# 10-Channel_SPI_Sensing_Circuit.net
KiCad netlist of a schematic drawn in Altium Designer
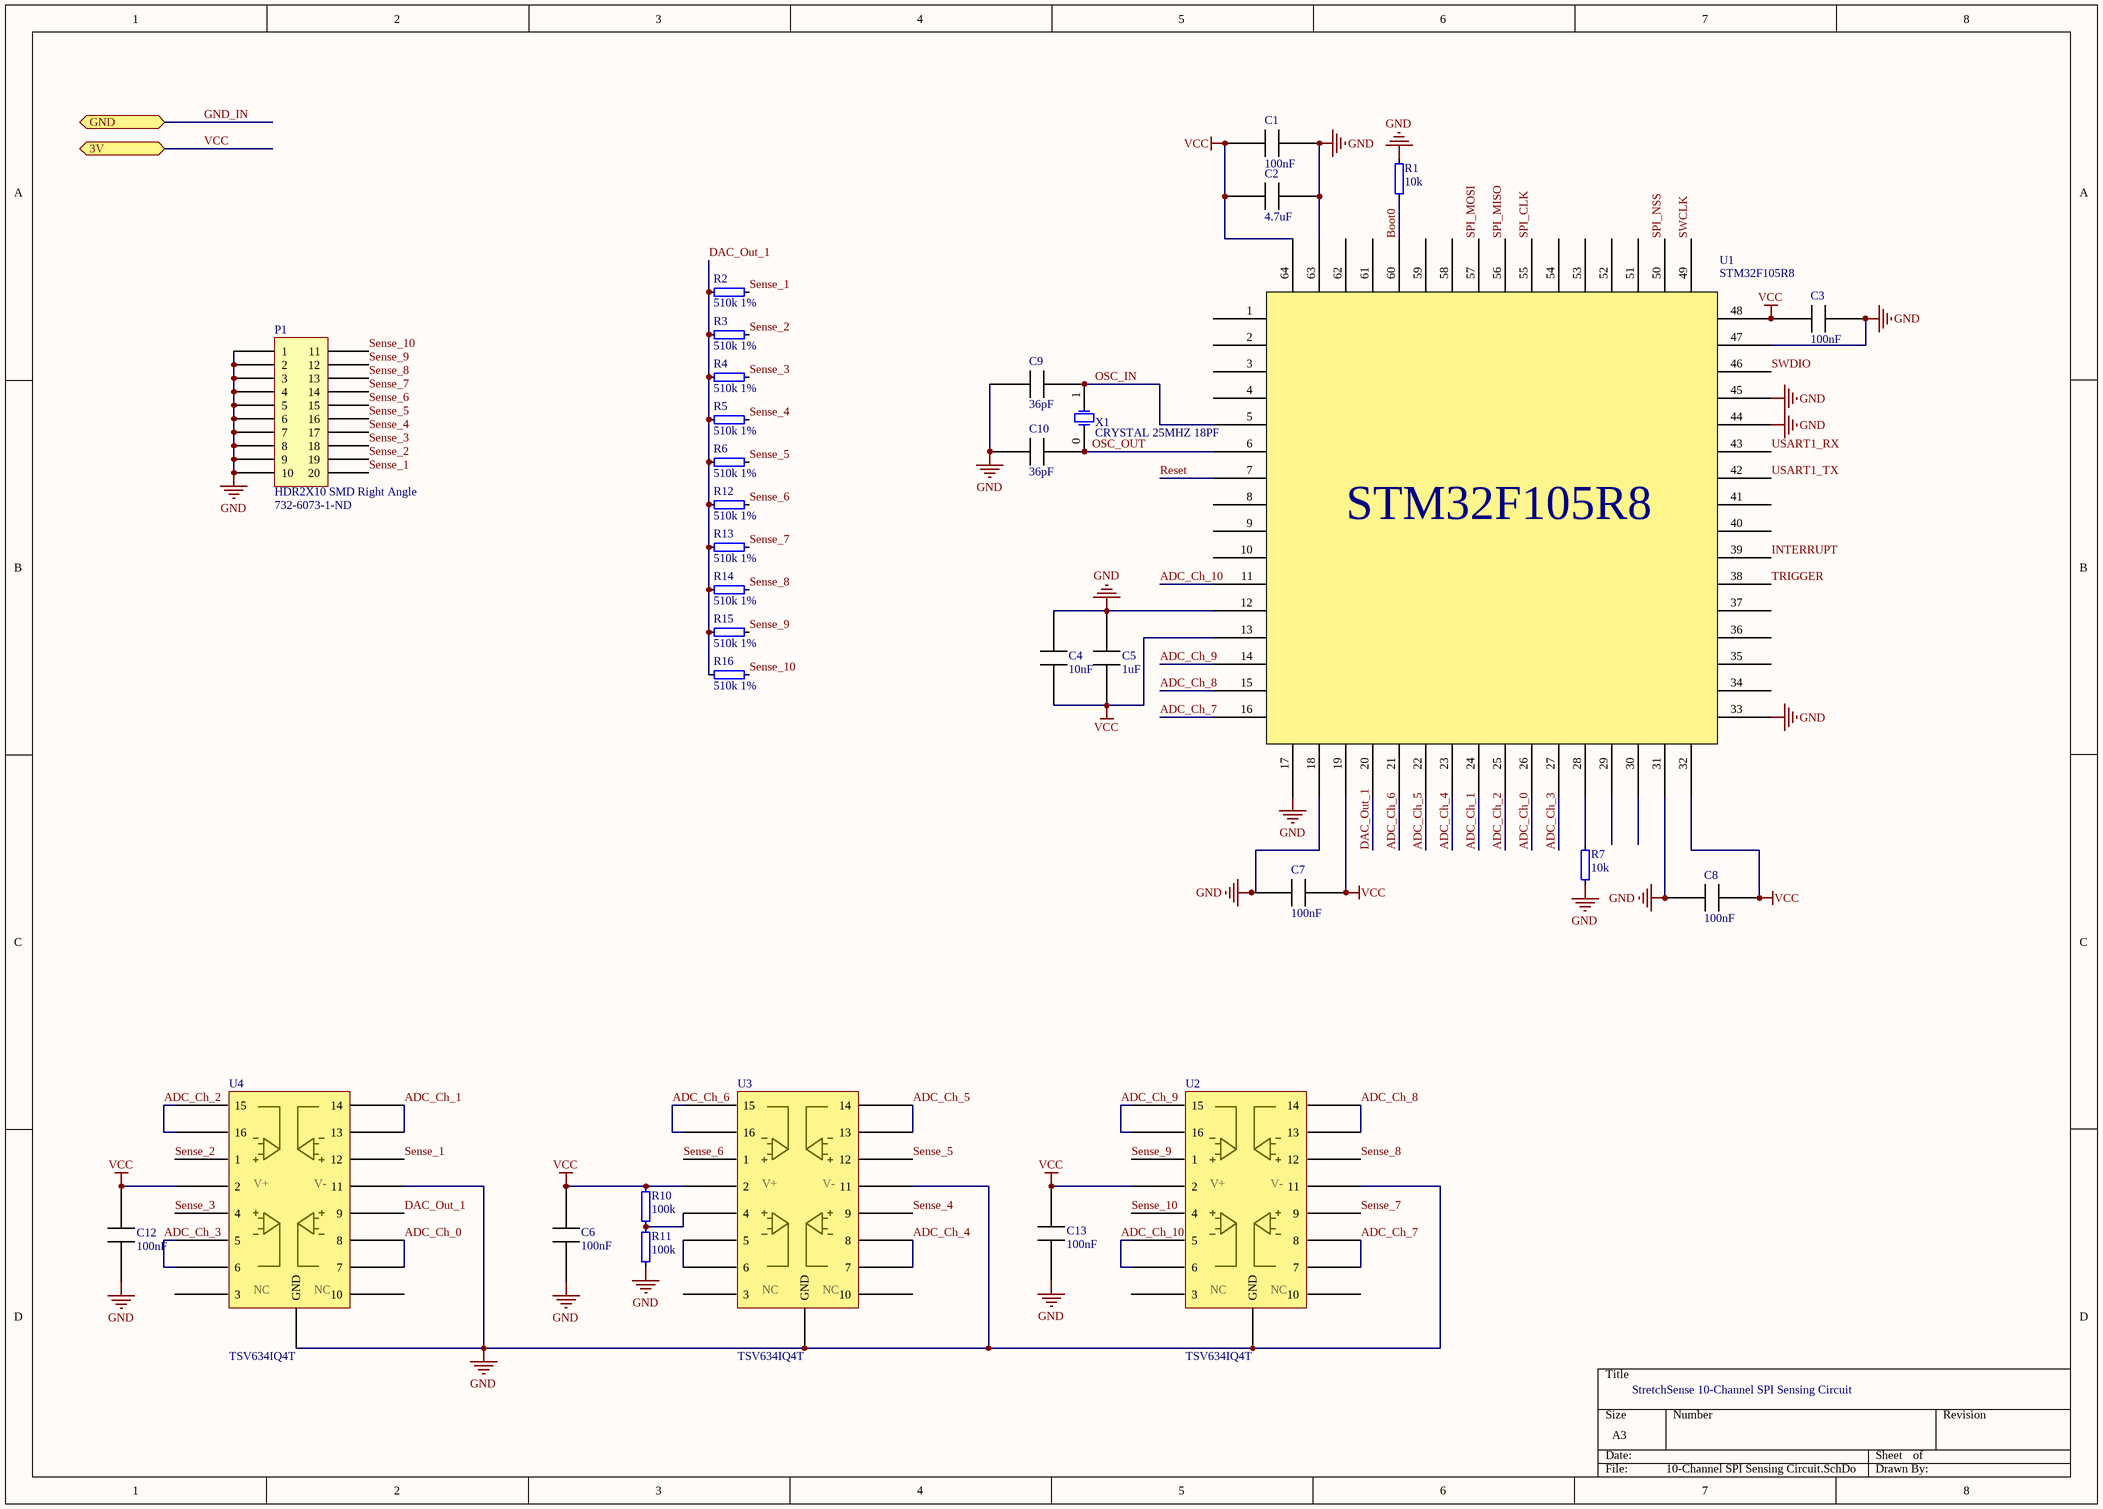
[diagram p0: 10-Channel SPI Sensing Circuit.SchDoc]

(export (version "E")
  (design (tool "Eeschema 10.0.6"))
  (components
    (comp (ref "C1")
      (value "100nF")
      (footprint "0402 Cap")
      (description "Capacitor")
      (fields
        (field (name "MANUFACTURER") "Samsung Electro-Mechanics America, Inc.")
        (field (name "MANUFACTURER PART NUMBER") "CL05B104KO5NNNC")
      )
      (libsource (lib "Fugu_V1") (part "Cap 0402 100nF 10%"))
    )
    (comp (ref "C2")
      (value "4.7uF")
      (footprint "0402 Cap")
      (description "Capacitor")
      (fields
        (field (name "MANUFACTURER") "TDK Corporation")
        (field (name "MANUFACTURER PART NUMBER") "C1005X5R1A475K050BC")
      )
      (libsource (lib "Gen3_V1") (part "Cap 0402 4.7uF 10%"))
    )
    (comp (ref "C3")
      (value "100nF")
      (footprint "0402 Cap")
      (description "Capacitor")
      (fields
        (field (name "MANUFACTURER") "Samsung Electro-Mechanics America, Inc.")
        (field (name "MANUFACTURER PART NUMBER") "CL05B104KO5NNNC")
      )
      (libsource (lib "Fugu_V1") (part "Cap 0402 100nF 10%"))
    )
    (comp (ref "C4")
      (value "10nF")
      (footprint "0402 Cap")
      (description "Capacitor")
      (fields
        (field (name "MANUFACTURER") "Samsung Electro-Mechanics America, Inc.")
        (field (name "MANUFACTURER PART NUMBER") "CL05B103KA5NNNC")
      )
      (libsource (lib "Gen3_V1") (part "Cap 0402 10nF 10%"))
    )
    (comp (ref "C5")
      (value "1uF")
      (footprint "0402 Cap")
      (description "Capacitor")
      (fields
        (field (name "MANUFACTURER") "Samsung Electro-Mechanics America, Inc.")
        (field (name "MANUFACTURER PART NUMBER") "CL05A105JQ5NNNC")
      )
      (libsource (lib "Fugu_V1") (part "Cap 0402 1uF 5%"))
    )
    (comp (ref "C6")
      (value "100nF")
      (footprint "0402 Cap")
      (description "Capacitor")
      (fields
        (field (name "MANUFACTURER") "Samsung Electro-Mechanics America, Inc.")
        (field (name "MANUFACTURER PART NUMBER") "CL05B104KO5NNNC")
      )
      (libsource (lib "Fugu_V1") (part "Cap 0402 100nF 10%"))
    )
    (comp (ref "C7")
      (value "100nF")
      (footprint "0402 Cap")
      (description "Capacitor")
      (fields
        (field (name "MANUFACTURER") "Samsung Electro-Mechanics America, Inc.")
        (field (name "MANUFACTURER PART NUMBER") "CL05B104KO5NNNC")
      )
      (libsource (lib "Fugu_V1") (part "Cap 0402 100nF 10%"))
    )
    (comp (ref "C8")
      (value "100nF")
      (footprint "0402 Cap")
      (description "Capacitor")
      (fields
        (field (name "MANUFACTURER") "Samsung Electro-Mechanics America, Inc.")
        (field (name "MANUFACTURER PART NUMBER") "CL05B104KO5NNNC")
      )
      (libsource (lib "Fugu_V1") (part "Cap 0402 100nF 10%"))
    )
    (comp (ref "C9")
      (value "36pF")
      (footprint "0402 Cap")
      (description "Capacitor")
      (fields
        (field (name "MANUFACTURER") "Samsung Electro-Mechanics America, Inc.")
        (field (name "MANUFACTURER PART NUMBER") "CL05C360JB5NNNC")
      )
      (libsource (lib "Fugu_V1") (part "Cap 36pF 0402"))
    )
    (comp (ref "C10")
      (value "36pF")
      (footprint "0402 Cap")
      (description "Capacitor")
      (fields
        (field (name "MANUFACTURER") "Samsung Electro-Mechanics America, Inc.")
        (field (name "MANUFACTURER PART NUMBER") "CL05C360JB5NNNC")
      )
      (libsource (lib "Fugu_V1") (part "Cap 36pF 0402"))
    )
    (comp (ref "C12")
      (value "100nF")
      (footprint "0402 Cap")
      (description "Capacitor")
      (fields
        (field (name "MANUFACTURER") "Samsung Electro-Mechanics America, Inc.")
        (field (name "MANUFACTURER PART NUMBER") "CL05B104KO5NNNC")
      )
      (libsource (lib "Fugu_V1") (part "Cap 0402 100nF 10%"))
    )
    (comp (ref "C13")
      (value "100nF")
      (footprint "0402 Cap")
      (description "Capacitor")
      (fields
        (field (name "MANUFACTURER") "Samsung Electro-Mechanics America, Inc.")
        (field (name "MANUFACTURER PART NUMBER") "CL05B104KO5NNNC")
      )
      (libsource (lib "Fugu_V1") (part "Cap 0402 100nF 10%"))
    )
    (comp (ref "P1")
      (value "HDR2X10 SMD Right Angle")
      (footprint "HDR2X10 SMD RIGHT")
      (description "Header")
      (fields
        (field (name "MANUFACTURER") "Wurth Electronics Inc")
        (field (name "MANUFACTURER PART NUMBER") "610120249121")
        (field (name "SUPPLIER PART NUMBER 1") "732-6073-1-ND")
      )
      (libsource (lib "Gen3_V1") (part "Header 2x10 SMD R/A 2.54mm"))
    )
    (comp (ref "R1")
      (value "10k")
      (footprint "0402 Res")
      (description "Resistor")
      (fields
        (field (name "MANUFACTURER") "Yageo")
        (field (name "MANUFACTURER PART NUMBER") "RC0402JR-0710KL")
      )
      (libsource (lib "Fugu_V1") (part "Res 0402 10k 5%"))
    )
    (comp (ref "R2")
      (value "510k 1%")
      (footprint "0402 Res")
      (description "Resistor")
      (fields
        (field (name "MANUFACTURER") "Yageo")
        (field (name "MANUFACTURER PART NUMBER") "RC0402FR-07510KL")
      )
      (libsource (lib "Fugu_V1") (part "Res 0402 510k 1%"))
    )
    (comp (ref "R3")
      (value "510k 1%")
      (footprint "0402 Res")
      (description "Resistor")
      (fields
        (field (name "MANUFACTURER") "Yageo")
        (field (name "MANUFACTURER PART NUMBER") "RC0402FR-07510KL")
      )
      (libsource (lib "Fugu_V1") (part "Res 0402 510k 1%"))
    )
    (comp (ref "R4")
      (value "510k 1%")
      (footprint "0402 Res")
      (description "Resistor")
      (fields
        (field (name "MANUFACTURER") "Yageo")
        (field (name "MANUFACTURER PART NUMBER") "RC0402FR-07510KL")
      )
      (libsource (lib "Fugu_V1") (part "Res 0402 510k 1%"))
    )
    (comp (ref "R5")
      (value "510k 1%")
      (footprint "0402 Res")
      (description "Resistor")
      (fields
        (field (name "MANUFACTURER") "Yageo")
        (field (name "MANUFACTURER PART NUMBER") "RC0402FR-07510KL")
      )
      (libsource (lib "Fugu_V1") (part "Res 0402 510k 1%"))
    )
    (comp (ref "R6")
      (value "510k 1%")
      (footprint "0402 Res")
      (description "Resistor")
      (fields
        (field (name "MANUFACTURER") "Yageo")
        (field (name "MANUFACTURER PART NUMBER") "RC0402FR-07510KL")
      )
      (libsource (lib "Fugu_V1") (part "Res 0402 510k 1%"))
    )
    (comp (ref "R7")
      (value "10k")
      (footprint "0402 Res")
      (description "Resistor")
      (fields
        (field (name "MANUFACTURER") "Yageo")
        (field (name "MANUFACTURER PART NUMBER") "RC0402JR-0710KL")
      )
      (libsource (lib "Fugu_V1") (part "Res 0402 10k 5%"))
    )
    (comp (ref "R10")
      (value "100k")
      (footprint "0402 Res")
      (description "Resistor")
      (fields
        (field (name "MANUFACTURER") "Yageo")
        (field (name "MANUFACTURER PART NUMBER") "RC0402FR-07100KL")
      )
      (libsource (lib "Fugu_V1") (part "Res 0402 100k 5%"))
    )
    (comp (ref "R11")
      (value "100k")
      (footprint "0402 Res")
      (description "Resistor")
      (fields
        (field (name "MANUFACTURER") "Yageo")
        (field (name "MANUFACTURER PART NUMBER") "RC0402FR-07100KL")
      )
      (libsource (lib "Fugu_V1") (part "Res 0402 100k 5%"))
    )
    (comp (ref "R12")
      (value "510k 1%")
      (footprint "0402 Res")
      (description "Resistor")
      (fields
        (field (name "MANUFACTURER") "Yageo")
        (field (name "MANUFACTURER PART NUMBER") "RC0402FR-07510KL")
      )
      (libsource (lib "Fugu_V1") (part "Res 0402 510k 1%"))
    )
    (comp (ref "R13")
      (value "510k 1%")
      (footprint "0402 Res")
      (description "Resistor")
      (fields
        (field (name "MANUFACTURER") "Yageo")
        (field (name "MANUFACTURER PART NUMBER") "RC0402FR-07510KL")
      )
      (libsource (lib "Fugu_V1") (part "Res 0402 510k 1%"))
    )
    (comp (ref "R14")
      (value "510k 1%")
      (footprint "0402 Res")
      (description "Resistor")
      (fields
        (field (name "MANUFACTURER") "Yageo")
        (field (name "MANUFACTURER PART NUMBER") "RC0402FR-07510KL")
      )
      (libsource (lib "Fugu_V1") (part "Res 0402 510k 1%"))
    )
    (comp (ref "R15")
      (value "510k 1%")
      (footprint "0402 Res")
      (description "Resistor")
      (fields
        (field (name "MANUFACTURER") "Yageo")
        (field (name "MANUFACTURER PART NUMBER") "RC0402FR-07510KL")
      )
      (libsource (lib "Fugu_V1") (part "Res 0402 510k 1%"))
    )
    (comp (ref "R16")
      (value "510k 1%")
      (footprint "0402 Res")
      (description "Resistor")
      (fields
        (field (name "MANUFACTURER") "Yageo")
        (field (name "MANUFACTURER PART NUMBER") "RC0402FR-07510KL")
      )
      (libsource (lib "Fugu_V1") (part "Res 0402 510k 1%"))
    )
    (comp (ref "U1")
      (value "STM32F105R8")
      (footprint "STM32F105R8")
      (description "Microcontroller")
      (fields
        (field (name "PART") "ST Microelectronics STM32F105R8")
        (field (name "MANUFACTURER") "STMicroelectronics")
      )
      (libsource (lib "Fugu_V1") (part "STM32F105R8"))
    )
    (comp (ref "U2")
      (value "TSV634IQ4T")
      (footprint "QFN-16")
      (description "Quad Opamp")
      (fields (field (name "MANUFACTURER") "STMicroelectronics"))
      (libsource (lib "Fugu_V1") (part "Quad Opamp TSV634IQ4T"))
    )
    (comp (ref "U3")
      (value "TSV634IQ4T")
      (footprint "QFN-16")
      (description "Quad Opamp")
      (fields (field (name "MANUFACTURER") "STMicroelectronics"))
      (libsource (lib "Fugu_V1") (part "Quad Opamp TSV634IQ4T"))
    )
    (comp (ref "U4")
      (value "TSV634IQ4T")
      (footprint "QFN-16")
      (description "Quad Opamp")
      (fields (field (name "MANUFACTURER") "STMicroelectronics"))
      (libsource (lib "Fugu_V1") (part "Quad Opamp TSV634IQ4T"))
    )
    (comp (ref "X1")
      (value "CRYSTAL 25MHZ 18PF")
      (footprint "CRYSTAL 24MHZ 18PF SMD")
      (description "445C25D24M00000")
      (fields
        (field (name "MANUFACTURER") "CTS-Frequency Controls")
        (field (name "MANUFACTURER PART NUMBER") "445C25D25M00000")
      )
      (libsource (lib "Gen3_V1") (part "CRYSTAL 25MHZ 18PF SMD"))
    )
  )
  (nets
    (net (code "1") (name "/ADC_Ch_0") (class "Default")
      (node (ref "U1") (pin "26") (pinfunction "Pin26_26") (pintype "passive"))
      (node (ref "U4") (pin "7") (pinfunction "7_7") (pintype "passive"))
      (node (ref "U4") (pin "8") (pinfunction "8_8") (pintype "passive"))
    )
    (net (code "2") (name "/ADC_Ch_1") (class "Default")
      (node (ref "U1") (pin "24") (pinfunction "Pin24_24") (pintype "passive"))
      (node (ref "U4") (pin "13") (pinfunction "13_13") (pintype "passive"))
      (node (ref "U4") (pin "14") (pinfunction "14_14") (pintype "passive"))
    )
    (net (code "3") (name "/ADC_Ch_2") (class "Default")
      (node (ref "U1") (pin "25") (pinfunction "Pin25_25") (pintype "passive"))
      (node (ref "U4") (pin "15") (pinfunction "15_15") (pintype "passive"))
      (node (ref "U4") (pin "16") (pinfunction "16_16") (pintype "passive"))
    )
    (net (code "4") (name "/ADC_Ch_3") (class "Default")
      (node (ref "U1") (pin "27") (pinfunction "Pin27_27") (pintype "passive"))
      (node (ref "U4") (pin "5") (pinfunction "5_5") (pintype "passive"))
      (node (ref "U4") (pin "6") (pinfunction "6_6") (pintype "passive"))
    )
    (net (code "5") (name "/ADC_Ch_4") (class "Default")
      (node (ref "U1") (pin "23") (pinfunction "Pin23_23") (pintype "passive"))
      (node (ref "U3") (pin "7") (pinfunction "7_7") (pintype "passive"))
      (node (ref "U3") (pin "8") (pinfunction "8_8") (pintype "passive"))
    )
    (net (code "6") (name "/ADC_Ch_5") (class "Default")
      (node (ref "U1") (pin "22") (pinfunction "Pin22_22") (pintype "passive"))
      (node (ref "U3") (pin "13") (pinfunction "13_13") (pintype "passive"))
      (node (ref "U3") (pin "14") (pinfunction "14_14") (pintype "passive"))
    )
    (net (code "7") (name "/ADC_Ch_6") (class "Default")
      (node (ref "U1") (pin "21") (pinfunction "Pin21_21") (pintype "passive"))
      (node (ref "U3") (pin "15") (pinfunction "15_15") (pintype "passive"))
      (node (ref "U3") (pin "16") (pinfunction "16_16") (pintype "passive"))
    )
    (net (code "8") (name "/ADC_Ch_7") (class "Default")
      (node (ref "U1") (pin "16") (pinfunction "Pin16_16") (pintype "passive"))
      (node (ref "U2") (pin "7") (pinfunction "7_7") (pintype "passive"))
      (node (ref "U2") (pin "8") (pinfunction "8_8") (pintype "passive"))
    )
    (net (code "9") (name "/ADC_Ch_8") (class "Default")
      (node (ref "U1") (pin "15") (pinfunction "Pin15_15") (pintype "passive"))
      (node (ref "U2") (pin "13") (pinfunction "13_13") (pintype "passive"))
      (node (ref "U2") (pin "14") (pinfunction "14_14") (pintype "passive"))
    )
    (net (code "10") (name "/ADC_Ch_9") (class "Default")
      (node (ref "U1") (pin "14") (pinfunction "Pin14_14") (pintype "passive"))
      (node (ref "U2") (pin "15") (pinfunction "15_15") (pintype "passive"))
      (node (ref "U2") (pin "16") (pinfunction "16_16") (pintype "passive"))
    )
    (net (code "11") (name "/ADC_Ch_10") (class "Default")
      (node (ref "U1") (pin "11") (pinfunction "Pin11_11") (pintype "passive"))
      (node (ref "U2") (pin "5") (pinfunction "5_5") (pintype "passive"))
      (node (ref "U2") (pin "6") (pinfunction "6_6") (pintype "passive"))
    )
    (net (code "12") (name "/Boot0") (class "Default")
      (node (ref "R1") (pin "2") (pinfunction "2_2") (pintype "passive"))
      (node (ref "U1") (pin "60") (pinfunction "Pin60_60") (pintype "passive"))
    )
    (net (code "13") (name "/DAC_Out_1") (class "Default")
      (node (ref "R12") (pin "1") (pinfunction "1_1") (pintype "passive"))
      (node (ref "R13") (pin "1") (pinfunction "1_1") (pintype "passive"))
      (node (ref "R14") (pin "1") (pinfunction "1_1") (pintype "passive"))
      (node (ref "R15") (pin "1") (pinfunction "1_1") (pintype "passive"))
      (node (ref "R16") (pin "1") (pinfunction "1_1") (pintype "passive"))
      (node (ref "R2") (pin "2") (pinfunction "2_2") (pintype "passive"))
      (node (ref "R3") (pin "2") (pinfunction "2_2") (pintype "passive"))
      (node (ref "R4") (pin "2") (pinfunction "2_2") (pintype "passive"))
      (node (ref "R5") (pin "2") (pinfunction "2_2") (pintype "passive"))
      (node (ref "R6") (pin "2") (pinfunction "2_2") (pintype "passive"))
      (node (ref "U1") (pin "20") (pinfunction "Pin20_20") (pintype "passive"))
      (node (ref "U4") (pin "9") (pinfunction "9_9") (pintype "passive"))
    )
    (net (code "14") (name "/INTERRUPT") (class "Default")
      (node (ref "U1") (pin "39") (pinfunction "Pin39_39") (pintype "passive"))
    )
    (net (code "15") (name "/OSC_IN") (class "Default")
      (node (ref "C9") (pin "1") (pinfunction "1_1") (pintype "passive"))
      (node (ref "U1") (pin "5") (pinfunction "Pin5_5") (pintype "passive"))
      (node (ref "X1") (pin "1") (pinfunction "OSC_IN_1") (pintype "passive"))
    )
    (net (code "16") (name "/OSC_OUT") (class "Default")
      (node (ref "C10") (pin "1") (pinfunction "1_1") (pintype "passive"))
      (node (ref "U1") (pin "6") (pinfunction "Pin6_6") (pintype "passive"))
      (node (ref "X1") (pin "0") (pinfunction "0_0") (pintype "passive"))
    )
    (net (code "17") (name "/Reset") (class "Default")
      (node (ref "U1") (pin "7") (pinfunction "Pin7_7") (pintype "passive"))
    )
    (net (code "18") (name "/SPI_CLK") (class "Default")
      (node (ref "U1") (pin "55") (pinfunction "Pin55_55") (pintype "passive"))
    )
    (net (code "19") (name "/SPI_MISO") (class "Default")
      (node (ref "U1") (pin "56") (pinfunction "Pin56_56") (pintype "passive"))
    )
    (net (code "20") (name "/SPI_MOSI") (class "Default")
      (node (ref "U1") (pin "57") (pinfunction "Pin57_57") (pintype "passive"))
    )
    (net (code "21") (name "/SPI_NSS") (class "Default")
      (node (ref "U1") (pin "50") (pinfunction "Pin50_50") (pintype "passive"))
    )
    (net (code "22") (name "/SWCLK") (class "Default")
      (node (ref "U1") (pin "49") (pinfunction "Pin49_49") (pintype "passive"))
    )
    (net (code "23") (name "/SWDIO") (class "Default")
      (node (ref "U1") (pin "46") (pinfunction "Pin46_46") (pintype "passive"))
    )
    (net (code "24") (name "/Sense_1") (class "Default")
      (node (ref "P1") (pin "20") (pinfunction "20_20") (pintype "passive"))
      (node (ref "R2") (pin "1") (pinfunction "1_1") (pintype "passive"))
      (node (ref "U4") (pin "12") (pinfunction "12_12") (pintype "passive"))
    )
    (net (code "25") (name "/Sense_2") (class "Default")
      (node (ref "P1") (pin "19") (pinfunction "19_19") (pintype "passive"))
      (node (ref "R3") (pin "1") (pinfunction "1_1") (pintype "passive"))
      (node (ref "U4") (pin "1") (pinfunction "1_1") (pintype "passive"))
    )
    (net (code "26") (name "/Sense_3") (class "Default")
      (node (ref "P1") (pin "18") (pinfunction "18_18") (pintype "passive"))
      (node (ref "R4") (pin "1") (pinfunction "1_1") (pintype "passive"))
      (node (ref "U4") (pin "4") (pinfunction "4_4") (pintype "passive"))
    )
    (net (code "27") (name "/Sense_4") (class "Default")
      (node (ref "P1") (pin "17") (pinfunction "17_17") (pintype "passive"))
      (node (ref "R5") (pin "1") (pinfunction "1_1") (pintype "passive"))
      (node (ref "U3") (pin "9") (pinfunction "9_9") (pintype "passive"))
    )
    (net (code "28") (name "/Sense_5") (class "Default")
      (node (ref "P1") (pin "16") (pinfunction "16_16") (pintype "passive"))
      (node (ref "R6") (pin "1") (pinfunction "1_1") (pintype "passive"))
      (node (ref "U3") (pin "12") (pinfunction "12_12") (pintype "passive"))
    )
    (net (code "29") (name "/Sense_6") (class "Default")
      (node (ref "P1") (pin "15") (pinfunction "15_15") (pintype "passive"))
      (node (ref "R12") (pin "2") (pinfunction "2_2") (pintype "passive"))
      (node (ref "U3") (pin "1") (pinfunction "1_1") (pintype "passive"))
    )
    (net (code "30") (name "/Sense_7") (class "Default")
      (node (ref "P1") (pin "14") (pinfunction "14_14") (pintype "passive"))
      (node (ref "R13") (pin "2") (pinfunction "2_2") (pintype "passive"))
      (node (ref "U2") (pin "9") (pinfunction "9_9") (pintype "passive"))
    )
    (net (code "31") (name "/Sense_8") (class "Default")
      (node (ref "P1") (pin "13") (pinfunction "13_13") (pintype "passive"))
      (node (ref "R14") (pin "2") (pinfunction "2_2") (pintype "passive"))
      (node (ref "U2") (pin "12") (pinfunction "12_12") (pintype "passive"))
    )
    (net (code "32") (name "/Sense_9") (class "Default")
      (node (ref "P1") (pin "12") (pinfunction "12_12") (pintype "passive"))
      (node (ref "R15") (pin "2") (pinfunction "2_2") (pintype "passive"))
      (node (ref "U2") (pin "1") (pinfunction "1_1") (pintype "passive"))
    )
    (net (code "33") (name "/Sense_10") (class "Default")
      (node (ref "P1") (pin "11") (pinfunction "11_11") (pintype "passive"))
      (node (ref "R16") (pin "2") (pinfunction "2_2") (pintype "passive"))
      (node (ref "U2") (pin "4") (pinfunction "4_4") (pintype "passive"))
    )
    (net (code "34") (name "/TRIGGER") (class "Default")
      (node (ref "U1") (pin "38") (pinfunction "Pin38_38") (pintype "passive"))
    )
    (net (code "35") (name "/USART1_RX") (class "Default")
      (node (ref "U1") (pin "43") (pinfunction "Pin43_43") (pintype "passive"))
    )
    (net (code "36") (name "/USART1_TX") (class "Default")
      (node (ref "U1") (pin "42") (pinfunction "Pin42_42") (pintype "passive"))
    )
    (net (code "37") (name "GND") (class "Default")
      (node (ref "C1") (pin "2") (pinfunction "2_2") (pintype "passive"))
      (node (ref "C10") (pin "2") (pinfunction "2_2") (pintype "passive"))
      (node (ref "C12") (pin "1") (pinfunction "1_1") (pintype "passive"))
      (node (ref "C13") (pin "1") (pinfunction "1_1") (pintype "passive"))
      (node (ref "C2") (pin "2") (pinfunction "2_2") (pintype "passive"))
      (node (ref "C3") (pin "2") (pinfunction "2_2") (pintype "passive"))
      (node (ref "C4") (pin "2") (pinfunction "2_2") (pintype "passive"))
      (node (ref "C5") (pin "1") (pinfunction "1_1") (pintype "passive"))
      (node (ref "C6") (pin "1") (pinfunction "1_1") (pintype "passive"))
      (node (ref "C7") (pin "1") (pinfunction "1_1") (pintype "passive"))
      (node (ref "C8") (pin "1") (pinfunction "1_1") (pintype "passive"))
      (node (ref "C9") (pin "2") (pinfunction "2_2") (pintype "passive"))
      (node (ref "P1") (pin "1") (pinfunction "1_1") (pintype "passive"))
      (node (ref "P1") (pin "10") (pinfunction "10_10") (pintype "passive"))
      (node (ref "P1") (pin "2") (pinfunction "2_2") (pintype "passive"))
      (node (ref "P1") (pin "3") (pinfunction "3_3") (pintype "passive"))
      (node (ref "P1") (pin "4") (pinfunction "4_4") (pintype "passive"))
      (node (ref "P1") (pin "5") (pinfunction "5_5") (pintype "passive"))
      (node (ref "P1") (pin "6") (pinfunction "6_6") (pintype "passive"))
      (node (ref "P1") (pin "7") (pinfunction "7_7") (pintype "passive"))
      (node (ref "P1") (pin "8") (pinfunction "8_8") (pintype "passive"))
      (node (ref "P1") (pin "9") (pinfunction "9_9") (pintype "passive"))
      (node (ref "R1") (pin "1") (pinfunction "1_1") (pintype "passive"))
      (node (ref "R11") (pin "1") (pinfunction "1_1") (pintype "passive"))
      (node (ref "R7") (pin "2") (pinfunction "2_2") (pintype "passive"))
      (node (ref "U1") (pin "12") (pinfunction "Pin12_12") (pintype "passive"))
      (node (ref "U1") (pin "17") (pinfunction "Pin17_17") (pintype "passive"))
      (node (ref "U1") (pin "18") (pinfunction "Pin18_18") (pintype "passive"))
      (node (ref "U1") (pin "31") (pinfunction "Pin31_31") (pintype "passive"))
      (node (ref "U1") (pin "33") (pinfunction "Pin33_33") (pintype "passive"))
      (node (ref "U1") (pin "44") (pinfunction "Pin44_44") (pintype "passive"))
      (node (ref "U1") (pin "45") (pinfunction "Pin45_45") (pintype "passive"))
      (node (ref "U1") (pin "47") (pinfunction "Pin47_47") (pintype "passive"))
      (node (ref "U1") (pin "63") (pinfunction "Pin63_63") (pintype "passive"))
      (node (ref "U2") (pin "11") (pinfunction "11_11") (pintype "passive"))
      (node (ref "U2") (pin "17") (pinfunction "GND_17") (pintype "passive"))
      (node (ref "U3") (pin "11") (pinfunction "11_11") (pintype "passive"))
      (node (ref "U3") (pin "17") (pinfunction "GND_17") (pintype "passive"))
      (node (ref "U4") (pin "11") (pinfunction "11_11") (pintype "passive"))
      (node (ref "U4") (pin "17") (pinfunction "GND_17") (pintype "passive"))
    )
    (net (code "38") (name "Net-(R10-Pad1)") (class "Default")
      (node (ref "R10") (pin "1") (pinfunction "1_1") (pintype "passive"))
      (node (ref "R11") (pin "2") (pinfunction "2_2") (pintype "passive"))
      (node (ref "U3") (pin "4") (pinfunction "4_4") (pintype "passive"))
    )
    (net (code "39") (name "Net-(U1-Pin28)") (class "Default")
      (node (ref "R7") (pin "1") (pinfunction "1_1") (pintype "passive"))
      (node (ref "U1") (pin "28") (pinfunction "Pin28_28") (pintype "passive"))
    )
    (net (code "40") (name "Net-(U3-Pad5)") (class "Default")
      (node (ref "U3") (pin "5") (pinfunction "5_5") (pintype "passive"))
      (node (ref "U3") (pin "6") (pinfunction "6_6") (pintype "passive"))
    )
    (net (code "41") (name "VCC") (class "Default")
      (node (ref "C1") (pin "1") (pinfunction "1_1") (pintype "passive"))
      (node (ref "C12") (pin "2") (pinfunction "2_2") (pintype "passive"))
      (node (ref "C13") (pin "2") (pinfunction "2_2") (pintype "passive"))
      (node (ref "C2") (pin "1") (pinfunction "1_1") (pintype "passive"))
      (node (ref "C3") (pin "1") (pinfunction "1_1") (pintype "passive"))
      (node (ref "C4") (pin "1") (pinfunction "1_1") (pintype "passive"))
      (node (ref "C5") (pin "2") (pinfunction "2_2") (pintype "passive"))
      (node (ref "C6") (pin "2") (pinfunction "2_2") (pintype "passive"))
      (node (ref "C7") (pin "2") (pinfunction "2_2") (pintype "passive"))
      (node (ref "C8") (pin "2") (pinfunction "2_2") (pintype "passive"))
      (node (ref "R10") (pin "2") (pinfunction "2_2") (pintype "passive"))
      (node (ref "U1") (pin "13") (pinfunction "Pin13_13") (pintype "passive"))
      (node (ref "U1") (pin "19") (pinfunction "Pin19_19") (pintype "passive"))
      (node (ref "U1") (pin "32") (pinfunction "Pin32_32") (pintype "passive"))
      (node (ref "U1") (pin "48") (pinfunction "Pin48_48") (pintype "passive"))
      (node (ref "U1") (pin "64") (pinfunction "Pin64_64") (pintype "passive"))
      (node (ref "U2") (pin "2") (pinfunction "2_2") (pintype "passive"))
      (node (ref "U3") (pin "2") (pinfunction "2_2") (pintype "passive"))
      (node (ref "U4") (pin "2") (pinfunction "2_2") (pintype "passive"))
    )
    (net (code "42") (name "unconnected-(U1-Pin1-Pad1)") (class "Default")
      (node (ref "U1") (pin "1") (pinfunction "Pin1_1") (pintype "passive"))
    )
    (net (code "43") (name "unconnected-(U1-Pin2-Pad2)") (class "Default")
      (node (ref "U1") (pin "2") (pinfunction "Pin2_2") (pintype "passive"))
    )
    (net (code "44") (name "unconnected-(U1-Pin3-Pad3)") (class "Default")
      (node (ref "U1") (pin "3") (pinfunction "Pin3_3") (pintype "passive"))
    )
    (net (code "45") (name "unconnected-(U1-Pin4-Pad4)") (class "Default")
      (node (ref "U1") (pin "4") (pinfunction "Pin4_4") (pintype "passive"))
    )
    (net (code "46") (name "unconnected-(U1-Pin8-Pad8)") (class "Default")
      (node (ref "U1") (pin "8") (pinfunction "Pin8_8") (pintype "passive"))
    )
    (net (code "47") (name "unconnected-(U1-Pin9-Pad9)") (class "Default")
      (node (ref "U1") (pin "9") (pinfunction "Pin9_9") (pintype "passive"))
    )
    (net (code "48") (name "unconnected-(U1-Pin10-Pad10)") (class "Default")
      (node (ref "U1") (pin "10") (pinfunction "Pin10_10") (pintype "passive"))
    )
    (net (code "49") (name "unconnected-(U1-Pin29-Pad29)") (class "Default")
      (node (ref "U1") (pin "29") (pinfunction "Pin29_29") (pintype "passive"))
    )
    (net (code "50") (name "unconnected-(U1-Pin30-Pad30)") (class "Default")
      (node (ref "U1") (pin "30") (pinfunction "Pin30_30") (pintype "passive"))
    )
    (net (code "51") (name "unconnected-(U1-Pin34-Pad34)") (class "Default")
      (node (ref "U1") (pin "34") (pinfunction "Pin34_34") (pintype "passive"))
    )
    (net (code "52") (name "unconnected-(U1-Pin35-Pad35)") (class "Default")
      (node (ref "U1") (pin "35") (pinfunction "Pin35_35") (pintype "passive"))
    )
    (net (code "53") (name "unconnected-(U1-Pin36-Pad36)") (class "Default")
      (node (ref "U1") (pin "36") (pinfunction "Pin36_36") (pintype "passive"))
    )
    (net (code "54") (name "unconnected-(U1-Pin37-Pad37)") (class "Default")
      (node (ref "U1") (pin "37") (pinfunction "Pin37_37") (pintype "passive"))
    )
    (net (code "55") (name "unconnected-(U1-Pin40-Pad40)") (class "Default")
      (node (ref "U1") (pin "40") (pinfunction "Pin40_40") (pintype "passive"))
    )
    (net (code "56") (name "unconnected-(U1-Pin41-Pad41)") (class "Default")
      (node (ref "U1") (pin "41") (pinfunction "Pin41_41") (pintype "passive"))
    )
    (net (code "57") (name "unconnected-(U1-Pin51-Pad51)") (class "Default")
      (node (ref "U1") (pin "51") (pinfunction "Pin51_51") (pintype "passive"))
    )
    (net (code "58") (name "unconnected-(U1-Pin52-Pad52)") (class "Default")
      (node (ref "U1") (pin "52") (pinfunction "Pin52_52") (pintype "passive"))
    )
    (net (code "59") (name "unconnected-(U1-Pin53-Pad53)") (class "Default")
      (node (ref "U1") (pin "53") (pinfunction "Pin53_53") (pintype "passive"))
    )
    (net (code "60") (name "unconnected-(U1-Pin54-Pad54)") (class "Default")
      (node (ref "U1") (pin "54") (pinfunction "Pin54_54") (pintype "passive"))
    )
    (net (code "61") (name "unconnected-(U1-Pin58-Pad58)") (class "Default")
      (node (ref "U1") (pin "58") (pinfunction "Pin58_58") (pintype "passive"))
    )
    (net (code "62") (name "unconnected-(U1-Pin59-Pad59)") (class "Default")
      (node (ref "U1") (pin "59") (pinfunction "Pin59_59") (pintype "passive"))
    )
    (net (code "63") (name "unconnected-(U1-Pin61-Pad61)") (class "Default")
      (node (ref "U1") (pin "61") (pinfunction "Pin61_61") (pintype "passive"))
    )
    (net (code "64") (name "unconnected-(U1-Pin62-Pad62)") (class "Default")
      (node (ref "U1") (pin "62") (pinfunction "Pin62_62") (pintype "passive"))
    )
    (net (code "65") (name "unconnected-(U2-Pad3)") (class "Default")
      (node (ref "U2") (pin "3") (pinfunction "3_3") (pintype "passive"))
    )
    (net (code "66") (name "unconnected-(U2-Pad10)") (class "Default")
      (node (ref "U2") (pin "10") (pinfunction "10_10") (pintype "passive"))
    )
    (net (code "67") (name "unconnected-(U3-Pad3)") (class "Default")
      (node (ref "U3") (pin "3") (pinfunction "3_3") (pintype "passive"))
    )
    (net (code "68") (name "unconnected-(U3-Pad10)") (class "Default")
      (node (ref "U3") (pin "10") (pinfunction "10_10") (pintype "passive"))
    )
    (net (code "69") (name "unconnected-(U4-Pad3)") (class "Default")
      (node (ref "U4") (pin "3") (pinfunction "3_3") (pintype "passive"))
    )
    (net (code "70") (name "unconnected-(U4-Pad10)") (class "Default")
      (node (ref "U4") (pin "10") (pinfunction "10_10") (pintype "passive"))
    )
  )
)
